# PowerInModule.net
KiCad netlist of a schematic drawn in EAGLE
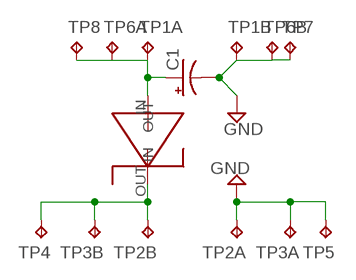
[diagram p0: schematic, sheet 1]

(export (version "E")
  (design (tool "Eeschema 10.0.6"))
  (components
    (comp (ref "C1")
      (value "CPOL-USE2.5-6")
      (footprint "eagle-import:E2,5-6")
      (libsource (lib "eagle-import") (part "CPOL-USE2.5-6"))
    )
    (comp (ref "TP1")
      (value "TP2P2-38-20")
      (footprint "eagle-import:P2-38-20")
      (libsource (lib "eagle-import") (part "TP2P2-38-20"))
    )
    (comp (ref "TP2")
      (value "TP2P2-38-20")
      (footprint "eagle-import:P2-38-20")
      (libsource (lib "eagle-import") (part "TP2P2-38-20"))
    )
    (comp (ref "TP3")
      (value "TP2P2-38-20")
      (footprint "eagle-import:P2-38-20")
      (libsource (lib "eagle-import") (part "TP2P2-38-20"))
    )
    (comp (ref "TP4")
      (value "TPPAD1-20")
      (footprint "eagle-import:P1-20")
      (libsource (lib "eagle-import") (part "TPPAD1-20"))
    )
    (comp (ref "TP5")
      (value "TPPAD1-20")
      (footprint "eagle-import:P1-20")
      (libsource (lib "eagle-import") (part "TPPAD1-20"))
    )
    (comp (ref "TP6")
      (value "TP2P2-38-20")
      (footprint "eagle-import:P2-38-20")
      (libsource (lib "eagle-import") (part "TP2P2-38-20"))
    )
    (comp (ref "TP7")
      (value "TPPAD1-20")
      (footprint "eagle-import:P1-20")
      (libsource (lib "eagle-import") (part "TPPAD1-20"))
    )
    (comp (ref "TP8")
      (value "TPPAD1-20")
      (footprint "eagle-import:P1-20")
      (libsource (lib "eagle-import") (part "TPPAD1-20"))
    )
    (comp (ref "U$1")
      (value "DO-214AB")
      (footprint "eagle-import:DO-214AB")
      (libsource (lib "eagle-import") (part "DO-214AB"))
    )
  )
  (nets
    (net (code "1") (name "GND") (class "Default")
      (node (ref "C1") (pin "-") (pinfunction "-_-") (pintype "passive"))
      (node (ref "TP1") (pin "TP-2") (pinfunction "TP_TP-2") (pintype "input"))
      (node (ref "TP2") (pin "TP-1") (pinfunction "TP_TP-1") (pintype "input"))
      (node (ref "TP3") (pin "TP-1") (pinfunction "TP_TP-1") (pintype "input"))
      (node (ref "TP5") (pin "TP") (pinfunction "TP_TP") (pintype "input"))
      (node (ref "TP6") (pin "TP-2") (pinfunction "TP_TP-2") (pintype "input"))
      (node (ref "TP7") (pin "TP") (pinfunction "TP_TP") (pintype "input"))
    )
    (net (code "2") (name "Net-(TP1A-TP)") (class "Default")
      (node (ref "C1") (pin "+") (pinfunction "+_+") (pintype "passive"))
      (node (ref "TP1") (pin "TP-1") (pinfunction "TP_TP-1") (pintype "input"))
      (node (ref "TP6") (pin "TP-1") (pinfunction "TP_TP-1") (pintype "input"))
      (node (ref "TP8") (pin "TP") (pinfunction "TP_TP") (pintype "input"))
      (node (ref "U$1") (pin "IN") (pinfunction "IN_IN") (pintype "bidirectional"))
    )
    (net (code "3") (name "Net-(TP2B-TP)") (class "Default")
      (node (ref "TP2") (pin "TP-2") (pinfunction "TP_TP-2") (pintype "input"))
      (node (ref "TP3") (pin "TP-2") (pinfunction "TP_TP-2") (pintype "input"))
      (node (ref "TP4") (pin "TP") (pinfunction "TP_TP") (pintype "input"))
      (node (ref "U$1") (pin "OUT") (pinfunction "OUT_OUT") (pintype "bidirectional"))
    )
  )
)
